# mainboard.net
KiCad netlist of a schematic drawn in EAGLE
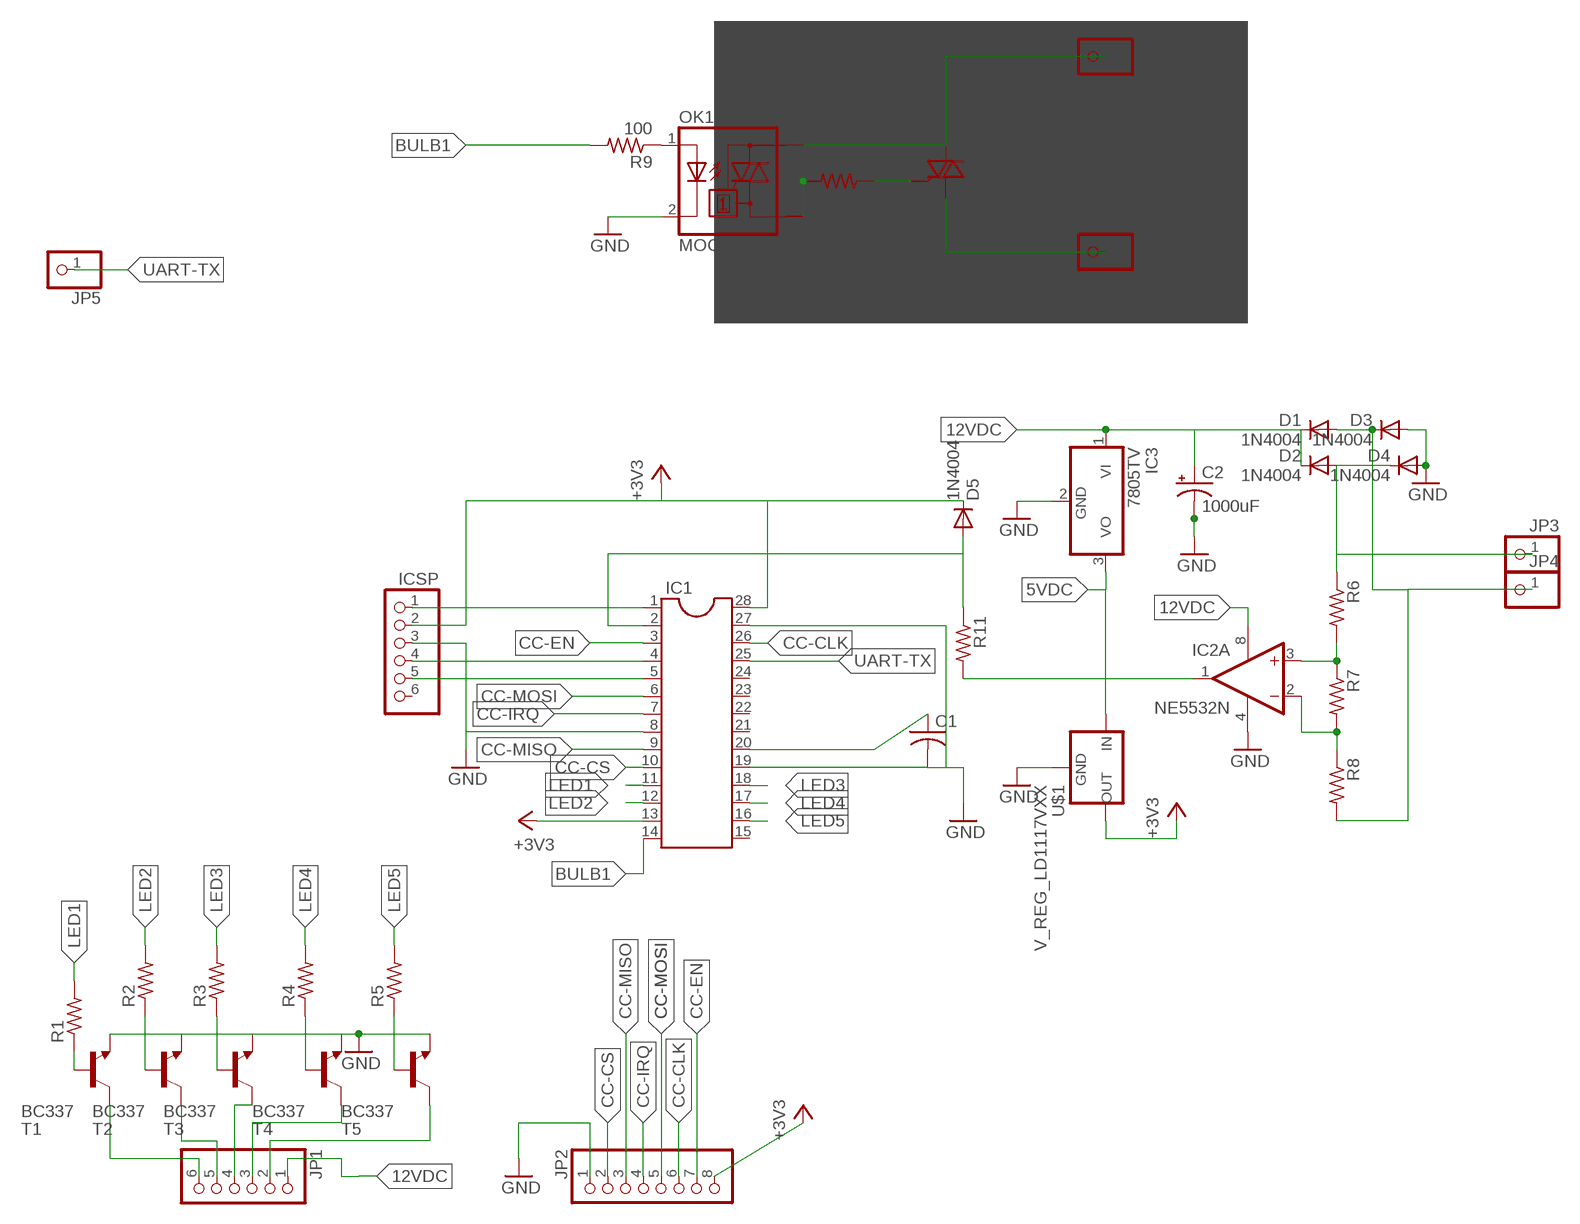
[diagram p0: schematic, sheet 1]

(export (version "E")
  (design (tool "Eeschema 10.0.6"))
  (components
    (comp (ref "230VAC1")
      (value "PINHD-1X1CB")
      (footprint "eagle-import:1X01-CLEANBIG")
      (libsource (lib "eagle-import") (part "PINHD-1X1CB"))
    )
    (comp (ref "230VAC2")
      (value "PINHD-1X1CB")
      (footprint "eagle-import:1X01-CLEANBIG")
      (libsource (lib "eagle-import") (part "PINHD-1X1CB"))
    )
    (comp (ref "BTB16")
      (value "BT138-V")
      (footprint "eagle-import:TO220BV")
      (libsource (lib "eagle-import") (part "BT138-V"))
    )
    (comp (ref "C1")
      (value "C-US025-024X044")
      (footprint "eagle-import:C025-024X044")
      (libsource (lib "eagle-import") (part "C-US025-024X044"))
    )
    (comp (ref "C2")
      (value "1000uF")
      (footprint "eagle-import:B45181B")
      (fields (field (name "MF") "RUBYCON") (field (name "MPN") "25ZL1000MEFC12.5X20"))
      (libsource (lib "eagle-import") (part "CPOL-USB45181B"))
    )
    (comp (ref "D1")
      (value "1N4004")
      (footprint "eagle-import:DO41-10")
      (fields (field (name "MF") "MULTICOMP"))
      (libsource (lib "eagle-import") (part "1N4004"))
    )
    (comp (ref "D2")
      (value "1N4004")
      (footprint "eagle-import:DO41-10")
      (fields (field (name "MF") "MULTICOMP"))
      (libsource (lib "eagle-import") (part "1N4004"))
    )
    (comp (ref "D3")
      (value "1N4004")
      (footprint "eagle-import:DO41-10")
      (fields (field (name "MF") "MULTICOMP"))
      (libsource (lib "eagle-import") (part "1N4004"))
    )
    (comp (ref "D4")
      (value "1N4004")
      (footprint "eagle-import:DO41-10")
      (fields (field (name "MF") "MULTICOMP"))
      (libsource (lib "eagle-import") (part "1N4004"))
    )
    (comp (ref "D5")
      (value "1N4004")
      (footprint "eagle-import:DO41-10")
      (fields (field (name "MF") "MULTICOMP"))
      (libsource (lib "eagle-import") (part "1N4004"))
    )
    (comp (ref "IC1")
      (value "DIL28-3")
      (footprint "eagle-import:DIL28-3")
      (libsource (lib "eagle-import") (part "DIL28-3"))
    )
    (comp (ref "IC2")
      (value "NE5532N")
      (footprint "eagle-import:DIL08")
      (fields
        (field (name "MF") "TEXAS INSTRUMENTS")
        (field (name "MPN") "NE5532AP")
        (field (name "OC_FARNELL") "1106091")
      )
      (libsource (lib "eagle-import") (part "NE5532N"))
    )
    (comp (ref "IC3")
      (value "7805TV")
      (footprint "eagle-import:TO220V")
      (libsource (lib "eagle-import") (part "78TV05"))
    )
    (comp (ref "ICSP")
      (value "PINHD-1X6")
      (footprint "eagle-import:1X06")
      (libsource (lib "eagle-import") (part "PINHD-1X6"))
    )
    (comp (ref "JP1")
      (value "PINHD-1X6")
      (footprint "eagle-import:1X06")
      (libsource (lib "eagle-import") (part "PINHD-1X6"))
    )
    (comp (ref "JP2")
      (value "PINHD-1X8BIG")
      (footprint "eagle-import:1X08-BIG")
      (libsource (lib "eagle-import") (part "PINHD-1X8BIG"))
    )
    (comp (ref "JP3")
      (value "PINHD-1X1CB")
      (footprint "eagle-import:1X01-CLEANBIG")
      (libsource (lib "eagle-import") (part "PINHD-1X1CB"))
    )
    (comp (ref "JP4")
      (value "PINHD-1X1CB")
      (footprint "eagle-import:1X01-CLEANBIG")
      (libsource (lib "eagle-import") (part "PINHD-1X1CB"))
    )
    (comp (ref "JP5")
      (value "PINHD-1X1")
      (footprint "eagle-import:1X01")
      (libsource (lib "eagle-import") (part "PINHD-1X1"))
    )
    (comp (ref "OK1")
      (value "MOC3020M")
      (footprint "eagle-import:DIL06")
      (fields
        (field (name "MF") "FAIRCHILD SEMICONDUCTOR")
        (field (name "MPN") "MOC3020-M")
        (field (name "OC_FARNELL") "unknown")
      )
      (libsource (lib "eagle-import") (part "MOC30M20"))
    )
    (comp (ref "R1")
      (value "R-US_0204/7")
      (footprint "eagle-import:0204_7")
      (libsource (lib "eagle-import") (part "R-US_0204/7"))
    )
    (comp (ref "R2")
      (value "R-US_0204/7")
      (footprint "eagle-import:0204_7")
      (libsource (lib "eagle-import") (part "R-US_0204/7"))
    )
    (comp (ref "R3")
      (value "R-US_0204/7")
      (footprint "eagle-import:0204_7")
      (libsource (lib "eagle-import") (part "R-US_0204/7"))
    )
    (comp (ref "R4")
      (value "R-US_0204/7")
      (footprint "eagle-import:0204_7")
      (libsource (lib "eagle-import") (part "R-US_0204/7"))
    )
    (comp (ref "R5")
      (value "R-US_0204/7")
      (footprint "eagle-import:0204_7")
      (libsource (lib "eagle-import") (part "R-US_0204/7"))
    )
    (comp (ref "R6")
      (value "R-US_0207/10")
      (footprint "eagle-import:0207_10")
      (libsource (lib "eagle-import") (part "R-US_0207/10"))
    )
    (comp (ref "R7")
      (value "R-US_0204/2V")
      (footprint "eagle-import:0204V")
      (libsource (lib "eagle-import") (part "R-US_0204/2V"))
    )
    (comp (ref "R8")
      (value "R-US_0207/10")
      (footprint "eagle-import:0207_10")
      (libsource (lib "eagle-import") (part "R-US_0207/10"))
    )
    (comp (ref "R9")
      (value "100")
      (footprint "eagle-import:0204_7")
      (libsource (lib "eagle-import") (part "R-US_0204/7"))
    )
    (comp (ref "R10")
      (value "R-US_0204/7")
      (footprint "eagle-import:0204_7")
      (libsource (lib "eagle-import") (part "R-US_0204/7"))
    )
    (comp (ref "R11")
      (value "R-US_0207/10")
      (footprint "eagle-import:0207_10")
      (libsource (lib "eagle-import") (part "R-US_0207/10"))
    )
    (comp (ref "T1")
      (value "BC337")
      (footprint "eagle-import:TO92-EBC-OVAL")
      (fields (field (name "MF") "FAIRCHILD SEMICONDUCTOR") (field (name "MPN") "BC33725TA"))
      (libsource (lib "eagle-import") (part "2N2222"))
    )
    (comp (ref "T2")
      (value "BC337")
      (footprint "eagle-import:TO92-EBC-OVAL")
      (fields (field (name "MF") "FAIRCHILD SEMICONDUCTOR") (field (name "MPN") "BC33725TA"))
      (libsource (lib "eagle-import") (part "2N2222"))
    )
    (comp (ref "T3")
      (value "BC337")
      (footprint "eagle-import:TO92-EBC-OVAL")
      (fields (field (name "MF") "FAIRCHILD SEMICONDUCTOR") (field (name "MPN") "BC33725TA"))
      (libsource (lib "eagle-import") (part "2N2222"))
    )
    (comp (ref "T4")
      (value "BC337")
      (footprint "eagle-import:TO92-EBC-OVAL")
      (fields (field (name "MF") "FAIRCHILD SEMICONDUCTOR") (field (name "MPN") "BC33725TA"))
      (libsource (lib "eagle-import") (part "2N2222"))
    )
    (comp (ref "T5")
      (value "BC337")
      (footprint "eagle-import:TO92-EBC-OVAL")
      (fields (field (name "MF") "FAIRCHILD SEMICONDUCTOR") (field (name "MPN") "BC33725TA"))
      (libsource (lib "eagle-import") (part "2N2222"))
    )
    (comp (ref "U$1")
      (value "V_REG_LD1117VXX")
      (footprint "eagle-import:78XXL")
      (libsource (lib "eagle-import") (part "V_REG_LD1117VXX"))
    )
  )
  (nets
    (net (code "1") (name "+3V3") (class "Default")
      (node (ref "D5") (pin "C") (pinfunction "C_C") (pintype "passive"))
      (node (ref "IC1") (pin "13") (pinfunction "13_13") (pintype "passive"))
      (node (ref "IC1") (pin "28") (pinfunction "28_28") (pintype "passive"))
      (node (ref "ICSP") (pin "2") (pinfunction "2_2") (pintype "passive"))
      (node (ref "JP2") (pin "8") (pinfunction "8_8") (pintype "passive"))
      (node (ref "U$1") (pin "GND") (pinfunction "OUT_GND") (pintype "output"))
    )
    (net (code "2") (name "5VDC") (class "Default")
      (node (ref "IC3") (pin "3") (pinfunction "VO_3") (pintype "passive"))
      (node (ref "U$1") (pin "OUT") (pinfunction "IN_OUT") (pintype "input"))
    )
    (net (code "3") (name "12VDC") (class "Default")
      (node (ref "C2") (pin "+") (pinfunction "+_+") (pintype "passive"))
      (node (ref "D1") (pin "C") (pinfunction "C_C") (pintype "passive"))
      (node (ref "D2") (pin "C") (pinfunction "C_C") (pintype "passive"))
      (node (ref "IC2") (pin "8") (pinfunction "V+_8") (pintype "power_in"))
      (node (ref "IC3") (pin "1") (pinfunction "VI_1") (pintype "input"))
      (node (ref "JP1") (pin "1") (pinfunction "1_1") (pintype "passive"))
    )
    (net (code "4") (name "BULB1") (class "Default")
      (node (ref "IC1") (pin "14") (pinfunction "14_14") (pintype "passive"))
      (node (ref "R9") (pin "2") (pinfunction "2_2") (pintype "passive"))
    )
    (net (code "5") (name "CC-CLK") (class "Default")
      (node (ref "IC1") (pin "26") (pinfunction "26_26") (pintype "passive"))
      (node (ref "JP2") (pin "6") (pinfunction "6_6") (pintype "passive"))
    )
    (net (code "6") (name "CC-CS") (class "Default")
      (node (ref "IC1") (pin "10") (pinfunction "10_10") (pintype "passive"))
      (node (ref "JP2") (pin "2") (pinfunction "2_2") (pintype "passive"))
    )
    (net (code "7") (name "CC-EN") (class "Default")
      (node (ref "IC1") (pin "3") (pinfunction "3_3") (pintype "passive"))
      (node (ref "JP2") (pin "7") (pinfunction "7_7") (pintype "passive"))
    )
    (net (code "8") (name "CC-IRQ") (class "Default")
      (node (ref "IC1") (pin "7") (pinfunction "7_7") (pintype "passive"))
      (node (ref "JP2") (pin "4") (pinfunction "4_4") (pintype "passive"))
    )
    (net (code "9") (name "CC-MISO") (class "Default")
      (node (ref "IC1") (pin "9") (pinfunction "9_9") (pintype "passive"))
      (node (ref "JP2") (pin "3") (pinfunction "3_3") (pintype "passive"))
    )
    (net (code "10") (name "CC-MOSI") (class "Default")
      (node (ref "IC1") (pin "6") (pinfunction "6_6") (pintype "passive"))
      (node (ref "JP2") (pin "5") (pinfunction "5_5") (pintype "passive"))
    )
    (net (code "11") (name "GND") (class "Default")
      (node (ref "C1") (pin "2") (pinfunction "2_2") (pintype "passive"))
      (node (ref "C2") (pin "-") (pinfunction "-_-") (pintype "passive"))
      (node (ref "D3") (pin "A") (pinfunction "A_A") (pintype "passive"))
      (node (ref "D4") (pin "A") (pinfunction "A_A") (pintype "passive"))
      (node (ref "IC1") (pin "19") (pinfunction "19_19") (pintype "passive"))
      (node (ref "IC1") (pin "27") (pinfunction "27_27") (pintype "passive"))
      (node (ref "IC1") (pin "8") (pinfunction "8_8") (pintype "passive"))
      (node (ref "IC2") (pin "4") (pinfunction "V-_4") (pintype "power_in"))
      (node (ref "IC3") (pin "2") (pinfunction "GND_2") (pintype "passive"))
      (node (ref "ICSP") (pin "3") (pinfunction "3_3") (pintype "passive"))
      (node (ref "JP2") (pin "1") (pinfunction "1_1") (pintype "passive"))
      (node (ref "OK1") (pin "2") (pinfunction "C_2") (pintype "passive"))
      (node (ref "T1") (pin "E") (pinfunction "E_E") (pintype "passive"))
      (node (ref "T5") (pin "E") (pinfunction "E_E") (pintype "passive"))
      (node (ref "U$1") (pin "IN") (pinfunction "GND_IN") (pintype "input"))
    )
    (net (code "12") (name "LED1") (class "Default")
      (node (ref "IC1") (pin "11") (pinfunction "11_11") (pintype "passive"))
      (node (ref "R1") (pin "2") (pinfunction "2_2") (pintype "passive"))
    )
    (net (code "13") (name "LED2") (class "Default")
      (node (ref "IC1") (pin "12") (pinfunction "12_12") (pintype "passive"))
      (node (ref "R2") (pin "2") (pinfunction "2_2") (pintype "passive"))
    )
    (net (code "14") (name "LED3") (class "Default")
      (node (ref "IC1") (pin "18") (pinfunction "18_18") (pintype "passive"))
      (node (ref "R3") (pin "2") (pinfunction "2_2") (pintype "passive"))
    )
    (net (code "15") (name "LED4") (class "Default")
      (node (ref "IC1") (pin "17") (pinfunction "17_17") (pintype "passive"))
      (node (ref "R4") (pin "2") (pinfunction "2_2") (pintype "passive"))
    )
    (net (code "16") (name "LED5") (class "Default")
      (node (ref "IC1") (pin "16") (pinfunction "16_16") (pintype "passive"))
      (node (ref "R5") (pin "2") (pinfunction "2_2") (pintype "passive"))
    )
    (net (code "17") (name "Net-(BTB16-A1)") (class "Default")
      (node (ref "230VAC2") (pin "1") (pinfunction "1_1") (pintype "passive"))
      (node (ref "BTB16") (pin "T1") (pinfunction "A1_T1") (pintype "passive"))
    )
    (net (code "18") (name "Net-(BTB16-A2)") (class "Default")
      (node (ref "230VAC1") (pin "1") (pinfunction "1_1") (pintype "passive"))
      (node (ref "BTB16") (pin "T2") (pinfunction "A2_T2") (pintype "passive"))
      (node (ref "OK1") (pin "6") (pinfunction "A2_6") (pintype "passive"))
    )
    (net (code "19") (name "Net-(BTB16-PadG)") (class "Default")
      (node (ref "BTB16") (pin "G") (pinfunction "G_G") (pintype "passive"))
      (node (ref "R10") (pin "1") (pinfunction "1_1") (pintype "passive"))
    )
    (net (code "20") (name "Net-(C1-Pad1)") (class "Default")
      (node (ref "C1") (pin "1") (pinfunction "1_1") (pintype "passive"))
      (node (ref "IC1") (pin "20") (pinfunction "20_20") (pintype "passive"))
    )
    (net (code "21") (name "Net-(D1-PadA)") (class "Default")
      (node (ref "D1") (pin "A") (pinfunction "A_A") (pintype "passive"))
      (node (ref "D3") (pin "C") (pinfunction "C_C") (pintype "passive"))
      (node (ref "JP4") (pin "1") (pinfunction "1_1") (pintype "passive"))
      (node (ref "R8") (pin "2") (pinfunction "2_2") (pintype "passive"))
    )
    (net (code "22") (name "Net-(D2-PadA)") (class "Default")
      (node (ref "D2") (pin "A") (pinfunction "A_A") (pintype "passive"))
      (node (ref "D4") (pin "C") (pinfunction "C_C") (pintype "passive"))
      (node (ref "JP3") (pin "1") (pinfunction "1_1") (pintype "passive"))
      (node (ref "R6") (pin "1") (pinfunction "1_1") (pintype "passive"))
    )
    (net (code "23") (name "Net-(D5-PadA)") (class "Default")
      (node (ref "D5") (pin "A") (pinfunction "A_A") (pintype "passive"))
      (node (ref "IC1") (pin "2") (pinfunction "2_2") (pintype "passive"))
      (node (ref "R11") (pin "1") (pinfunction "1_1") (pintype "passive"))
    )
    (net (code "24") (name "Net-(IC1-Pad1)") (class "Default")
      (node (ref "IC1") (pin "1") (pinfunction "1_1") (pintype "passive"))
      (node (ref "ICSP") (pin "1") (pinfunction "1_1") (pintype "passive"))
    )
    (net (code "25") (name "Net-(IC1-Pad4)") (class "Default")
      (node (ref "IC1") (pin "4") (pinfunction "4_4") (pintype "passive"))
      (node (ref "ICSP") (pin "4") (pinfunction "4_4") (pintype "passive"))
    )
    (net (code "26") (name "Net-(IC1-Pad5)") (class "Default")
      (node (ref "IC1") (pin "5") (pinfunction "5_5") (pintype "passive"))
      (node (ref "ICSP") (pin "5") (pinfunction "5_5") (pintype "passive"))
    )
    (net (code "27") (name "Net-(IC2A-+IN)") (class "Default")
      (node (ref "IC2") (pin "3") (pinfunction "+IN_3") (pintype "input"))
      (node (ref "R6") (pin "2") (pinfunction "2_2") (pintype "passive"))
      (node (ref "R7") (pin "1") (pinfunction "1_1") (pintype "passive"))
    )
    (net (code "28") (name "Net-(IC2A--IN)") (class "Default")
      (node (ref "IC2") (pin "2") (pinfunction "-IN_2") (pintype "input"))
      (node (ref "R7") (pin "2") (pinfunction "2_2") (pintype "passive"))
      (node (ref "R8") (pin "1") (pinfunction "1_1") (pintype "passive"))
    )
    (net (code "29") (name "Net-(IC2A-OUT)") (class "Default")
      (node (ref "IC2") (pin "1") (pinfunction "OUT_1") (pintype "output"))
      (node (ref "R11") (pin "2") (pinfunction "2_2") (pintype "passive"))
    )
    (net (code "30") (name "Net-(JP1-Pad2)") (class "Default")
      (node (ref "JP1") (pin "2") (pinfunction "2_2") (pintype "passive"))
      (node (ref "T5") (pin "C") (pinfunction "C_C") (pintype "passive"))
    )
    (net (code "31") (name "Net-(JP1-Pad3)") (class "Default")
      (node (ref "JP1") (pin "3") (pinfunction "3_3") (pintype "passive"))
      (node (ref "T4") (pin "C") (pinfunction "C_C") (pintype "passive"))
    )
    (net (code "32") (name "Net-(JP1-Pad4)") (class "Default")
      (node (ref "JP1") (pin "4") (pinfunction "4_4") (pintype "passive"))
      (node (ref "T3") (pin "C") (pinfunction "C_C") (pintype "passive"))
    )
    (net (code "33") (name "Net-(JP1-Pad5)") (class "Default")
      (node (ref "JP1") (pin "5") (pinfunction "5_5") (pintype "passive"))
      (node (ref "T2") (pin "C") (pinfunction "C_C") (pintype "passive"))
    )
    (net (code "34") (name "Net-(JP1-Pad6)") (class "Default")
      (node (ref "JP1") (pin "6") (pinfunction "6_6") (pintype "passive"))
      (node (ref "T1") (pin "C") (pinfunction "C_C") (pintype "passive"))
    )
    (net (code "35") (name "Net-(OK1-A)") (class "Default")
      (node (ref "OK1") (pin "1") (pinfunction "A_1") (pintype "passive"))
      (node (ref "R9") (pin "1") (pinfunction "1_1") (pintype "passive"))
    )
    (net (code "36") (name "Net-(OK1-A1)") (class "Default")
      (node (ref "OK1") (pin "4") (pinfunction "A1_4") (pintype "passive"))
      (node (ref "R10") (pin "2") (pinfunction "2_2") (pintype "passive"))
    )
    (net (code "37") (name "Net-(R1-Pad1)") (class "Default")
      (node (ref "R1") (pin "1") (pinfunction "1_1") (pintype "passive"))
      (node (ref "T1") (pin "B") (pinfunction "B_B") (pintype "passive"))
    )
    (net (code "38") (name "Net-(R2-Pad1)") (class "Default")
      (node (ref "R2") (pin "1") (pinfunction "1_1") (pintype "passive"))
      (node (ref "T2") (pin "B") (pinfunction "B_B") (pintype "passive"))
    )
    (net (code "39") (name "Net-(R3-Pad1)") (class "Default")
      (node (ref "R3") (pin "1") (pinfunction "1_1") (pintype "passive"))
      (node (ref "T3") (pin "B") (pinfunction "B_B") (pintype "passive"))
    )
    (net (code "40") (name "Net-(R4-Pad1)") (class "Default")
      (node (ref "R4") (pin "1") (pinfunction "1_1") (pintype "passive"))
      (node (ref "T4") (pin "B") (pinfunction "B_B") (pintype "passive"))
    )
    (net (code "41") (name "Net-(R5-Pad1)") (class "Default")
      (node (ref "R5") (pin "1") (pinfunction "1_1") (pintype "passive"))
      (node (ref "T5") (pin "B") (pinfunction "B_B") (pintype "passive"))
    )
    (net (code "42") (name "UART-TX") (class "Default")
      (node (ref "IC1") (pin "25") (pinfunction "25_25") (pintype "passive"))
      (node (ref "JP5") (pin "1") (pinfunction "1_1") (pintype "passive"))
    )
    (net (code "43") (name "unconnected-(IC1-Pad15)") (class "Default")
      (node (ref "IC1") (pin "15") (pinfunction "15_15") (pintype "passive"))
    )
    (net (code "44") (name "unconnected-(IC1-Pad21)") (class "Default")
      (node (ref "IC1") (pin "21") (pinfunction "21_21") (pintype "passive"))
    )
    (net (code "45") (name "unconnected-(IC1-Pad22)") (class "Default")
      (node (ref "IC1") (pin "22") (pinfunction "22_22") (pintype "passive"))
    )
    (net (code "46") (name "unconnected-(IC1-Pad23)") (class "Default")
      (node (ref "IC1") (pin "23") (pinfunction "23_23") (pintype "passive"))
    )
    (net (code "47") (name "unconnected-(IC1-Pad24)") (class "Default")
      (node (ref "IC1") (pin "24") (pinfunction "24_24") (pintype "passive"))
    )
    (net (code "48") (name "unconnected-(ICSP-Pad6)") (class "Default")
      (node (ref "ICSP") (pin "6") (pinfunction "6_6") (pintype "passive"))
    )
    (net (code "49") (name "unconnected-(T2-PadE)") (class "Default")
      (node (ref "T2") (pin "E") (pinfunction "E_E") (pintype "passive"))
    )
    (net (code "50") (name "unconnected-(T3-PadE)") (class "Default")
      (node (ref "T3") (pin "E") (pinfunction "E_E") (pintype "passive"))
    )
    (net (code "51") (name "unconnected-(T4-PadE)") (class "Default")
      (node (ref "T4") (pin "E") (pinfunction "E_E") (pintype "passive"))
    )
  )
)
